# ATtiny85_Contact_Sensor.net
KiCad netlist of a schematic drawn in EAGLE
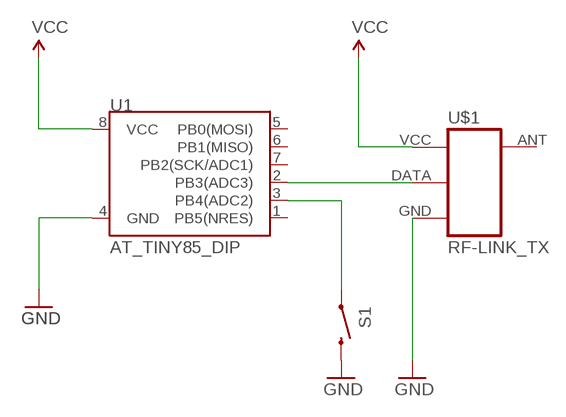
[diagram p0: schematic, sheet 1]

(export (version "E")
  (design (tool "Eeschema 10.0.6"))
  (components
    (comp (ref "S1")
      (value "SWITCH-MOMENTARY-2PTH")
      (footprint "eagle-import:TACTILE-PTH")
      (libsource (lib "eagle-import") (part "SWITCH-MOMENTARY-2PTH"))
    )
    (comp (ref "U$1")
      (value "RF-LINK_TX")
      (footprint "eagle-import:RF-LINK_TX")
      (libsource (lib "eagle-import") (part "RF-LINK_TX"))
    )
    (comp (ref "U1")
      (value "AT_TINY85_DIP")
      (footprint "eagle-import:DIP08")
      (libsource (lib "eagle-import") (part "ATTINY45TINY45-20-DIP"))
    )
  )
  (nets
    (net (code "1") (name "GND") (class "Default")
      (node (ref "S1") (pin "3") (pinfunction "2_3") (pintype "passive"))
      (node (ref "U$1") (pin "GND") (pinfunction "GND_GND") (pintype "power_in"))
      (node (ref "U1") (pin "4") (pinfunction "GND_4") (pintype "bidirectional"))
    )
    (net (code "2") (name "Net-(U1-PB3(ADC3))") (class "Default")
      (node (ref "U$1") (pin "DATA") (pinfunction "DATA_DATA") (pintype "input"))
      (node (ref "U1") (pin "2") (pinfunction "PB3(ADC3)_2") (pintype "bidirectional"))
    )
    (net (code "3") (name "Net-(U1-PB4(ADC2))") (class "Default")
      (node (ref "S1") (pin "1") (pinfunction "1_1") (pintype "passive"))
      (node (ref "U1") (pin "3") (pinfunction "PB4(ADC2)_3") (pintype "bidirectional"))
    )
    (net (code "4") (name "VCC") (class "Default")
      (node (ref "U$1") (pin "VCC") (pinfunction "+5V_VCC") (pintype "power_in"))
      (node (ref "U1") (pin "8") (pinfunction "VCC_8") (pintype "bidirectional"))
    )
    (net (code "5") (name "unconnected-(U$1-PadANT)") (class "Default")
      (node (ref "U$1") (pin "ANT") (pinfunction "ANT_ANT") (pintype "passive"))
    )
    (net (code "6") (name "unconnected-(U1-PB0(MOSI)-Pad5)") (class "Default")
      (node (ref "U1") (pin "5") (pinfunction "PB0(MOSI)_5") (pintype "bidirectional"))
    )
    (net (code "7") (name "unconnected-(U1-PB1(MISO)-Pad6)") (class "Default")
      (node (ref "U1") (pin "6") (pinfunction "PB1(MISO)_6") (pintype "bidirectional"))
    )
    (net (code "8") (name "unconnected-(U1-PB2(SCK{slash}ADC1)-Pad7)") (class "Default")
      (node (ref "U1") (pin "7") (pinfunction "PB2(SCK/ADC1)_7") (pintype "bidirectional"))
    )
    (net (code "9") (name "unconnected-(U1-PB5(NRES)-Pad1)") (class "Default")
      (node (ref "U1") (pin "1") (pinfunction "PB5(NRES)_1") (pintype "bidirectional"))
    )
  )
)
